# barebones_arduino_v10.net
KiCad netlist of a schematic drawn in EAGLE
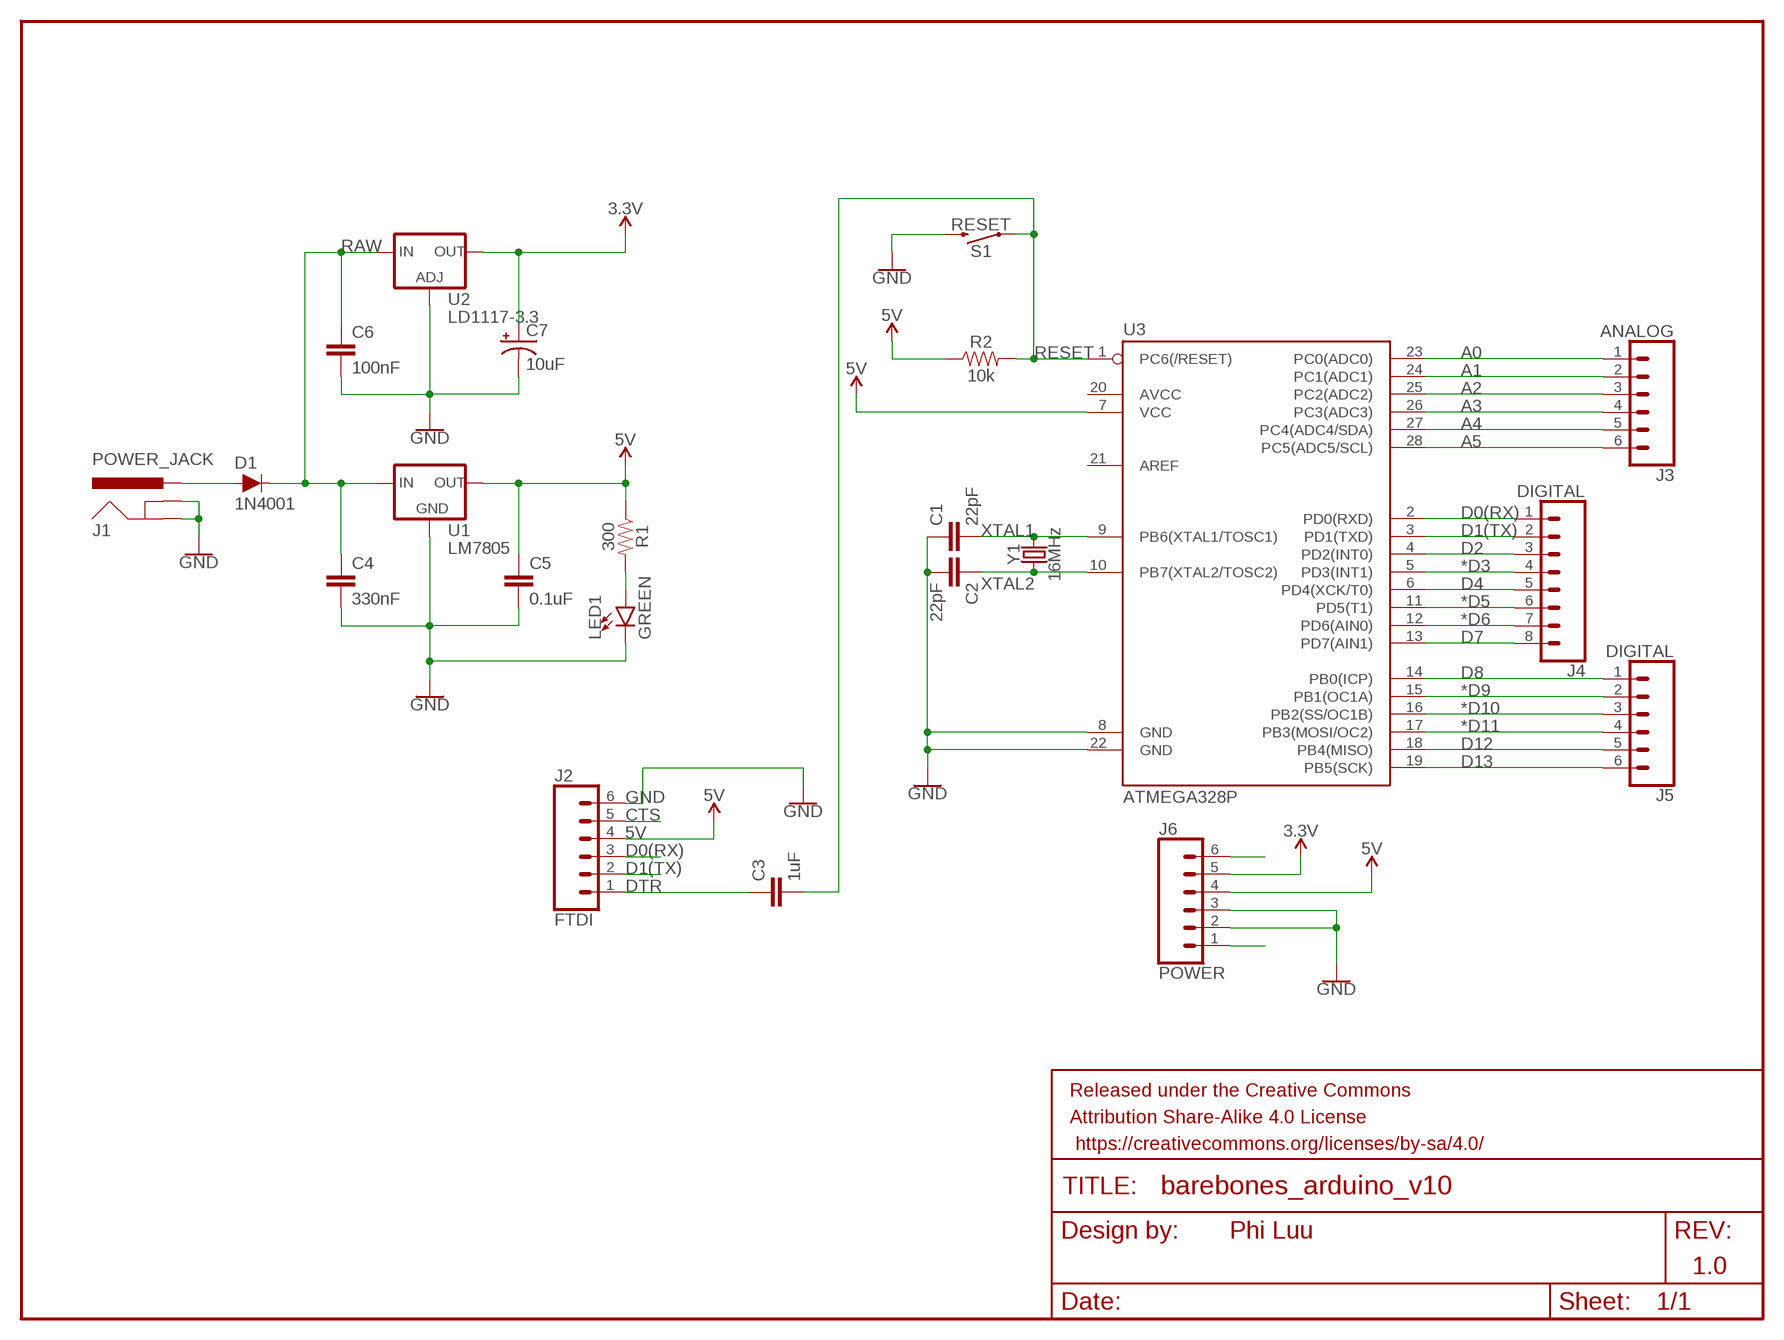
[diagram p0: schematic, sheet 1]

(export (version "E")
  (design (tool "Eeschema 10.0.6"))
  (components
    (comp (ref "C1")
      (value "22pF")
      (footprint "eagle-import:CAP-PTH-2.54")
      (libsource (lib "eagle-import") (part "22PF-PTH-2.54MM-200V-5%"))
    )
    (comp (ref "C2")
      (value "22pF")
      (footprint "eagle-import:CAP-PTH-2.54")
      (libsource (lib "eagle-import") (part "22PF-PTH-2.54MM-200V-5%"))
    )
    (comp (ref "C3")
      (value "1uF")
      (footprint "eagle-import:CAP-PTH-SMALL-KIT")
      (libsource (lib "eagle-import") (part "0.1UF-KIT-EZ-50V-20%"))
    )
    (comp (ref "C4")
      (value "330nF")
      (footprint "eagle-import:CAP-PTH-SMALL-KIT")
      (libsource (lib "eagle-import") (part "0.1UF-KIT-EZ-50V-20%"))
    )
    (comp (ref "C5")
      (value "0.1uF")
      (footprint "eagle-import:CAP-PTH-SMALL-KIT")
      (libsource (lib "eagle-import") (part "0.1UF-KIT-EZ-50V-20%"))
    )
    (comp (ref "C6")
      (value "100nF")
      (footprint "eagle-import:CAP-PTH-SMALL-KIT")
      (libsource (lib "eagle-import") (part "0.1UF-KIT-EZ-50V-20%"))
    )
    (comp (ref "C7")
      (value "10uF")
      (footprint "eagle-import:CPOL-RADIAL-2.5MM-5MM")
      (libsource (lib "eagle-import") (part "10UF-POLAR-RADIAL-2.5MM-25V-20%"))
    )
    (comp (ref "D1")
      (value "1N4001")
      (footprint "eagle-import:DIODE-1N4001")
      (libsource (lib "eagle-import") (part "DIODE-PTH"))
    )
    (comp (ref "FRAME1")
      (value "FRAME-LETTER")
      (footprint "eagle-import:CREATIVE_COMMONS")
      (libsource (lib "eagle-import") (part "FRAME-LETTER"))
    )
    (comp (ref "J1")
      (value "POWER_JACK")
      (footprint "eagle-import:POWER_JACK_PTH")
      (libsource (lib "eagle-import") (part "POWER_JACK"))
    )
    (comp (ref "J2")
      (value "FTDI")
      (footprint "eagle-import:1X06")
      (libsource (lib "eagle-import") (part "CONN_06SILK_FEMALE_PTH"))
    )
    (comp (ref "J3")
      (value "ANALOG")
      (footprint "eagle-import:1X06")
      (libsource (lib "eagle-import") (part "CONN_06SILK_FEMALE_PTH"))
    )
    (comp (ref "J4")
      (value "DIGITAL")
      (footprint "eagle-import:1X08")
      (libsource (lib "eagle-import") (part "CONN_08{dblquote}"))
    )
    (comp (ref "J5")
      (value "DIGITAL")
      (footprint "eagle-import:1X06")
      (libsource (lib "eagle-import") (part "CONN_06SILK_FEMALE_PTH"))
    )
    (comp (ref "J6")
      (value "POWER")
      (footprint "eagle-import:1X06")
      (libsource (lib "eagle-import") (part "CONN_06SILK_FEMALE_PTH"))
    )
    (comp (ref "LED1")
      (value "GREEN")
      (footprint "eagle-import:LED_5MM")
      (libsource (lib "eagle-import") (part "LED5MM"))
    )
    (comp (ref "R1")
      (value "300")
      (footprint "eagle-import:AXIAL-0.3")
      (libsource (lib "eagle-import") (part "1KOHM-HORIZ-1/4W-5%"))
    )
    (comp (ref "R2")
      (value "10k")
      (footprint "eagle-import:AXIAL-0.3")
      (libsource (lib "eagle-import") (part "10KOHM-HORIZ-1/4W-5%"))
    )
    (comp (ref "S1")
      (value "RESET")
      (footprint "eagle-import:TACTILE_SWITCH_PTH_6.0MM")
      (libsource (lib "eagle-import") (part "MOMENTARY-SWITCH-SPST-PTH-6.0MM"))
    )
    (comp (ref "U1")
      (value "LM7805")
      (footprint "eagle-import:TO220-IGO")
      (libsource (lib "eagle-import") (part "V_REG_78XXSINK"))
    )
    (comp (ref "U2")
      (value "LD1117-3.3")
      (footprint "eagle-import:TO220-ADJ")
      (libsource (lib "eagle-import") (part "V_REG_317SINK"))
    )
    (comp (ref "U3")
      (value "ATMEGA328P")
      (footprint "eagle-import:DIP28")
      (libsource (lib "eagle-import") (part "ATMEGA328P_PDIP"))
    )
    (comp (ref "Y1")
      (value "16MHz")
      (footprint "eagle-import:HC49US")
      (libsource (lib "eagle-import") (part "CRYSTAL-16MHZPTH-HC49US"))
    )
  )
  (nets
    (net (code "1") (name "/*D3") (class "Default")
      (node (ref "J4") (pin "4") (pinfunction "4_4") (pintype "passive"))
      (node (ref "U3") (pin "5") (pinfunction "PD3(INT1)_5") (pintype "bidirectional"))
    )
    (net (code "2") (name "/*D5") (class "Default")
      (node (ref "J4") (pin "6") (pinfunction "6_6") (pintype "passive"))
      (node (ref "U3") (pin "11") (pinfunction "PD5(T1)_11") (pintype "bidirectional"))
    )
    (net (code "3") (name "/*D6") (class "Default")
      (node (ref "J4") (pin "7") (pinfunction "7_7") (pintype "passive"))
      (node (ref "U3") (pin "12") (pinfunction "PD6(AIN0)_12") (pintype "bidirectional"))
    )
    (net (code "4") (name "/*D9") (class "Default")
      (node (ref "J5") (pin "2") (pinfunction "2_2") (pintype "passive"))
      (node (ref "U3") (pin "15") (pinfunction "PB1(OC1A)_15") (pintype "bidirectional"))
    )
    (net (code "5") (name "/*D10") (class "Default")
      (node (ref "J5") (pin "3") (pinfunction "3_3") (pintype "passive"))
      (node (ref "U3") (pin "16") (pinfunction "PB2(SS/OC1B)_16") (pintype "bidirectional"))
    )
    (net (code "6") (name "/*D11") (class "Default")
      (node (ref "J5") (pin "4") (pinfunction "4_4") (pintype "passive"))
      (node (ref "U3") (pin "17") (pinfunction "PB3(MOSI/OC2)_17") (pintype "bidirectional"))
    )
    (net (code "7") (name "/A0") (class "Default")
      (node (ref "J3") (pin "1") (pinfunction "1_1") (pintype "passive"))
      (node (ref "U3") (pin "23") (pinfunction "PC0(ADC0)_23") (pintype "bidirectional"))
    )
    (net (code "8") (name "/A1") (class "Default")
      (node (ref "J3") (pin "2") (pinfunction "2_2") (pintype "passive"))
      (node (ref "U3") (pin "24") (pinfunction "PC1(ADC1)_24") (pintype "bidirectional"))
    )
    (net (code "9") (name "/A2") (class "Default")
      (node (ref "J3") (pin "3") (pinfunction "3_3") (pintype "passive"))
      (node (ref "U3") (pin "25") (pinfunction "PC2(ADC2)_25") (pintype "bidirectional"))
    )
    (net (code "10") (name "/A3") (class "Default")
      (node (ref "J3") (pin "4") (pinfunction "4_4") (pintype "passive"))
      (node (ref "U3") (pin "26") (pinfunction "PC3(ADC3)_26") (pintype "bidirectional"))
    )
    (net (code "11") (name "/A4") (class "Default")
      (node (ref "J3") (pin "5") (pinfunction "5_5") (pintype "passive"))
      (node (ref "U3") (pin "27") (pinfunction "PC4(ADC4/SDA)_27") (pintype "bidirectional"))
    )
    (net (code "12") (name "/A5") (class "Default")
      (node (ref "J3") (pin "6") (pinfunction "6_6") (pintype "passive"))
      (node (ref "U3") (pin "28") (pinfunction "PC5(ADC5/SCL)_28") (pintype "bidirectional"))
    )
    (net (code "13") (name "/CTS") (class "Default")
      (node (ref "J2") (pin "5") (pinfunction "5_5") (pintype "passive"))
    )
    (net (code "14") (name "/D0(RX)") (class "Default")
      (node (ref "J2") (pin "3") (pinfunction "3_3") (pintype "passive"))
      (node (ref "J4") (pin "1") (pinfunction "1_1") (pintype "passive"))
      (node (ref "U3") (pin "2") (pinfunction "PD0(RXD)_2") (pintype "bidirectional"))
    )
    (net (code "15") (name "/D1(TX)") (class "Default")
      (node (ref "J2") (pin "2") (pinfunction "2_2") (pintype "passive"))
      (node (ref "J4") (pin "2") (pinfunction "2_2") (pintype "passive"))
      (node (ref "U3") (pin "3") (pinfunction "PD1(TXD)_3") (pintype "bidirectional"))
    )
    (net (code "16") (name "/D2") (class "Default")
      (node (ref "J4") (pin "3") (pinfunction "3_3") (pintype "passive"))
      (node (ref "U3") (pin "4") (pinfunction "PD2(INT0)_4") (pintype "bidirectional"))
    )
    (net (code "17") (name "/D4") (class "Default")
      (node (ref "J4") (pin "5") (pinfunction "5_5") (pintype "passive"))
      (node (ref "U3") (pin "6") (pinfunction "PD4(XCK/T0)_6") (pintype "bidirectional"))
    )
    (net (code "18") (name "/D7") (class "Default")
      (node (ref "J4") (pin "8") (pinfunction "8_8") (pintype "passive"))
      (node (ref "U3") (pin "13") (pinfunction "PD7(AIN1)_13") (pintype "bidirectional"))
    )
    (net (code "19") (name "/D8") (class "Default")
      (node (ref "J5") (pin "1") (pinfunction "1_1") (pintype "passive"))
      (node (ref "U3") (pin "14") (pinfunction "PB0(ICP)_14") (pintype "bidirectional"))
    )
    (net (code "20") (name "/D12") (class "Default")
      (node (ref "J5") (pin "5") (pinfunction "5_5") (pintype "passive"))
      (node (ref "U3") (pin "18") (pinfunction "PB4(MISO)_18") (pintype "bidirectional"))
    )
    (net (code "21") (name "/D13") (class "Default")
      (node (ref "J5") (pin "6") (pinfunction "6_6") (pintype "passive"))
      (node (ref "U3") (pin "19") (pinfunction "PB5(SCK)_19") (pintype "bidirectional"))
    )
    (net (code "22") (name "/DTR") (class "Default")
      (node (ref "C3") (pin "1") (pinfunction "1_1") (pintype "passive"))
      (node (ref "J2") (pin "1") (pinfunction "1_1") (pintype "passive"))
    )
    (net (code "23") (name "/RAW") (class "Default")
      (node (ref "C4") (pin "1") (pinfunction "1_1") (pintype "passive"))
      (node (ref "C6") (pin "1") (pinfunction "1_1") (pintype "passive"))
      (node (ref "D1") (pin "C") (pinfunction "C_C") (pintype "passive"))
      (node (ref "J6") (pin "1") (pinfunction "1_1") (pintype "passive"))
      (node (ref "U1") (pin "IN") (pinfunction "IN_IN") (pintype "input"))
      (node (ref "U2") (pin "IN") (pinfunction "IN_IN") (pintype "input"))
    )
    (net (code "24") (name "/RESET") (class "Default")
      (node (ref "C3") (pin "2") (pinfunction "2_2") (pintype "passive"))
      (node (ref "J6") (pin "6") (pinfunction "6_6") (pintype "passive"))
      (node (ref "R2") (pin "P$2") (pinfunction "2_P$2") (pintype "passive"))
      (node (ref "S1") (pin "1") (pinfunction "1_1") (pintype "passive"))
      (node (ref "U3") (pin "1") (pinfunction "PC6(/RESET)_1") (pintype "bidirectional"))
    )
    (net (code "25") (name "/XTAL1") (class "Default")
      (node (ref "C1") (pin "2") (pinfunction "2_2") (pintype "passive"))
      (node (ref "U3") (pin "9") (pinfunction "PB6(XTAL1/TOSC1)_9") (pintype "bidirectional"))
      (node (ref "Y1") (pin "2") (pinfunction "2_2") (pintype "passive"))
    )
    (net (code "26") (name "/XTAL2") (class "Default")
      (node (ref "C2") (pin "1") (pinfunction "1_1") (pintype "passive"))
      (node (ref "U3") (pin "10") (pinfunction "PB7(XTAL2/TOSC2)_10") (pintype "bidirectional"))
      (node (ref "Y1") (pin "1") (pinfunction "1_1") (pintype "passive"))
    )
    (net (code "27") (name "3.3V") (class "Default")
      (node (ref "C7") (pin "1") (pinfunction "+_1") (pintype "passive"))
      (node (ref "J6") (pin "5") (pinfunction "5_5") (pintype "passive"))
      (node (ref "U2") (pin "OUT") (pinfunction "OUT_OUT") (pintype "output"))
    )
    (net (code "28") (name "5V") (class "Default")
      (node (ref "C5") (pin "1") (pinfunction "1_1") (pintype "passive"))
      (node (ref "J2") (pin "4") (pinfunction "4_4") (pintype "passive"))
      (node (ref "J6") (pin "4") (pinfunction "4_4") (pintype "passive"))
      (node (ref "R1") (pin "P$1") (pinfunction "1_P$1") (pintype "passive"))
      (node (ref "R2") (pin "P$1") (pinfunction "1_P$1") (pintype "passive"))
      (node (ref "U1") (pin "OUT") (pinfunction "OUT_OUT") (pintype "passive"))
      (node (ref "U3") (pin "7") (pinfunction "VCC_7") (pintype "bidirectional"))
    )
    (net (code "29") (name "GND") (class "Default")
      (node (ref "C1") (pin "1") (pinfunction "1_1") (pintype "passive"))
      (node (ref "C2") (pin "2") (pinfunction "2_2") (pintype "passive"))
      (node (ref "C4") (pin "2") (pinfunction "2_2") (pintype "passive"))
      (node (ref "C5") (pin "2") (pinfunction "2_2") (pintype "passive"))
      (node (ref "C6") (pin "2") (pinfunction "2_2") (pintype "passive"))
      (node (ref "C7") (pin "2") (pinfunction "-_2") (pintype "passive"))
      (node (ref "J1") (pin "GND") (pinfunction "GND_GND") (pintype "bidirectional"))
      (node (ref "J1") (pin "GNDBREAK") (pinfunction "GNDBREAK_GNDBREAK") (pintype "bidirectional"))
      (node (ref "J2") (pin "6") (pinfunction "6_6") (pintype "passive"))
      (node (ref "J6") (pin "2") (pinfunction "2_2") (pintype "passive"))
      (node (ref "J6") (pin "3") (pinfunction "3_3") (pintype "passive"))
      (node (ref "LED1") (pin "K") (pinfunction "C_K") (pintype "passive"))
      (node (ref "S1") (pin "3") (pinfunction "2_3") (pintype "passive"))
      (node (ref "U1") (pin "GND") (pinfunction "GND_GND") (pintype "input"))
      (node (ref "U2") (pin "ADJ") (pinfunction "ADJ_ADJ") (pintype "input"))
      (node (ref "U3") (pin "22") (pinfunction "GND_22") (pintype "bidirectional"))
      (node (ref "U3") (pin "8") (pinfunction "GND_8") (pintype "bidirectional"))
    )
    (net (code "30") (name "Net-(D1-PadA)") (class "Default")
      (node (ref "D1") (pin "A") (pinfunction "A_A") (pintype "passive"))
      (node (ref "J1") (pin "PWR") (pinfunction "PWR_PWR") (pintype "bidirectional"))
    )
    (net (code "31") (name "Net-(R1-2)") (class "Default")
      (node (ref "LED1") (pin "A") (pinfunction "A_A") (pintype "passive"))
      (node (ref "R1") (pin "P$2") (pinfunction "2_P$2") (pintype "passive"))
    )
    (net (code "32") (name "unconnected-(U3-AREF-Pad21)") (class "Default")
      (node (ref "U3") (pin "21") (pinfunction "AREF_21") (pintype "bidirectional"))
    )
    (net (code "33") (name "unconnected-(U3-AVCC-Pad20)") (class "Default")
      (node (ref "U3") (pin "20") (pinfunction "AVCC_20") (pintype "bidirectional"))
    )
  )
)
